# u_build_45w_power_supply.net
KiCad netlist of a schematic drawn in EAGLE
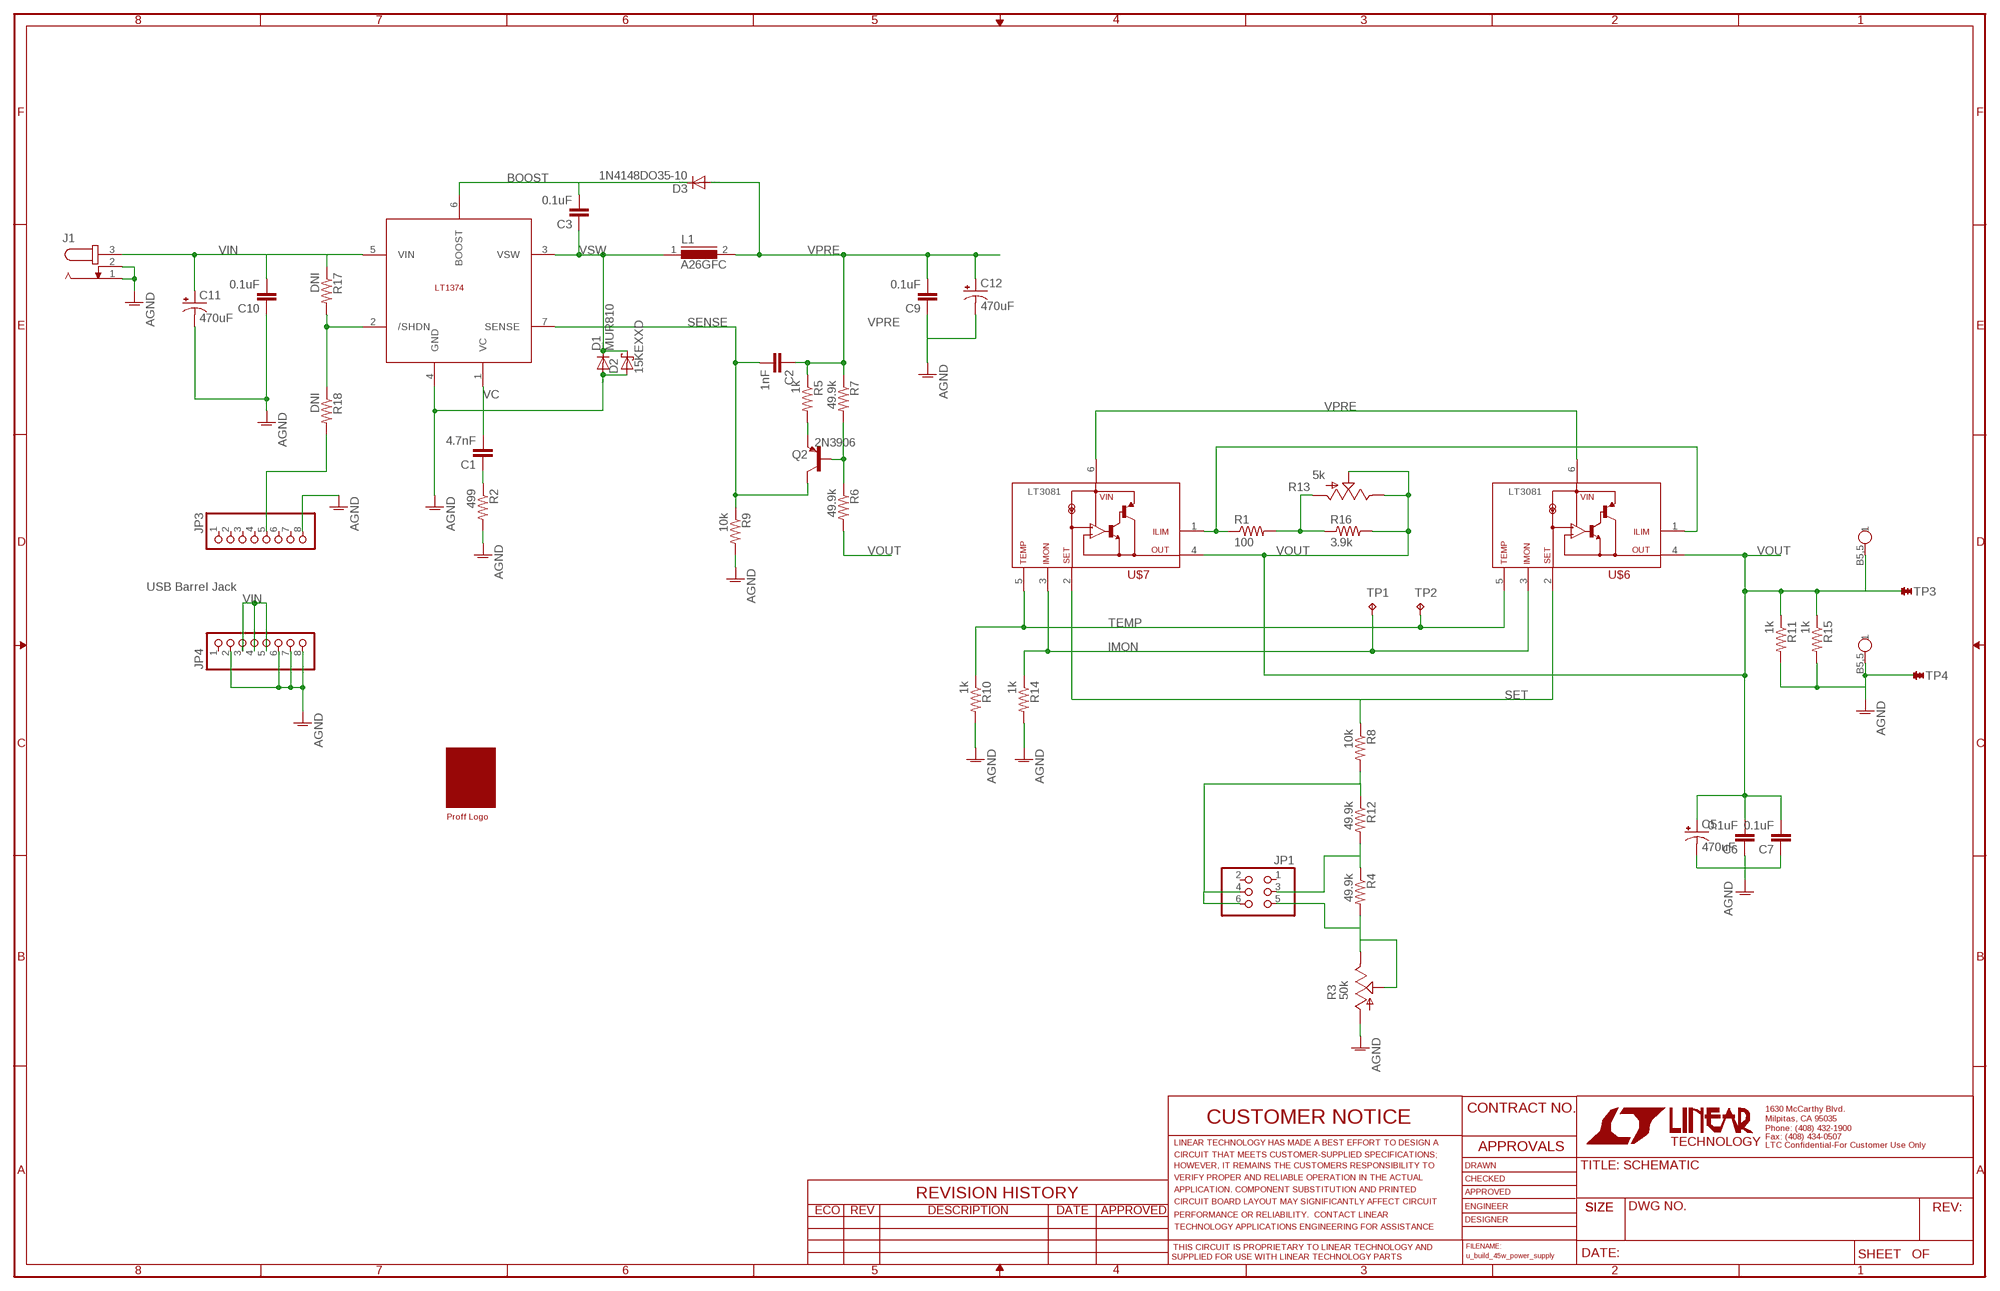
[diagram p0: schematic, sheet 1]

(export (version "E")
  (design (tool "Eeschema 10.0.6"))
  (components
    (comp (ref "C1")
      (value "4.7nF")
      (footprint "eagle-import:C050-025X075")
      (libsource (lib "eagle-import") (part "C-EU050-025X075"))
    )
    (comp (ref "C2")
      (value "1nF")
      (footprint "eagle-import:C050-025X075")
      (libsource (lib "eagle-import") (part "C-EU050-025X075"))
    )
    (comp (ref "C3")
      (value "0.1uF")
      (footprint "eagle-import:C050-025X075")
      (libsource (lib "eagle-import") (part "C-EU050-025X075"))
    )
    (comp (ref "C5")
      (value "470uF")
      (footprint "eagle-import:E5-10,5")
      (libsource (lib "eagle-import") (part "CPOL-USE5-10.5"))
    )
    (comp (ref "C6")
      (value "0.1uF")
      (footprint "eagle-import:C050-045X075")
      (libsource (lib "eagle-import") (part "C-EU050-045X075"))
    )
    (comp (ref "C7")
      (value "0.1uF")
      (footprint "eagle-import:C050-045X075")
      (libsource (lib "eagle-import") (part "C-EU050-045X075"))
    )
    (comp (ref "C9")
      (value "0.1uF")
      (footprint "eagle-import:C050-045X075")
      (libsource (lib "eagle-import") (part "C-EU050-045X075"))
    )
    (comp (ref "C10")
      (value "0.1uF")
      (footprint "eagle-import:C050-045X075")
      (libsource (lib "eagle-import") (part "C-EU050-045X075"))
    )
    (comp (ref "C11")
      (value "470uF")
      (footprint "eagle-import:E5-10,5")
      (libsource (lib "eagle-import") (part "CPOL-USE5-10.5"))
    )
    (comp (ref "C12")
      (value "470uF")
      (footprint "eagle-import:E5-10,5")
      (libsource (lib "eagle-import") (part "CPOL-USE5-10.5"))
    )
    (comp (ref "D1")
      (value "MUR810")
      (footprint "eagle-import:TO220ACS")
      (libsource (lib "eagle-import") (part "MUR810"))
    )
    (comp (ref "D2")
      (value "15KEXXD")
      (footprint "eagle-import:DO201T15")
      (libsource (lib "eagle-import") (part "15KEXXD"))
    )
    (comp (ref "D3")
      (value "1N4148DO35-10")
      (footprint "eagle-import:DO35-10")
      (libsource (lib "eagle-import") (part "1N4148DO35-10"))
    )
    (comp (ref "IC2")
      (value "LT1374TO220-7")
      (footprint "eagle-import:LT3081")
      (libsource (lib "eagle-import") (part "LT1374TO220-7"))
    )
    (comp (ref "J1")
      (value "JACK-PLUG0")
      (footprint "eagle-import:SPC4077")
      (libsource (lib "eagle-import") (part "JACK-PLUG0"))
    )
    (comp (ref "J5")
      (value "BAN_JACK1")
      (footprint "eagle-import:PC_BAN_JACK")
      (libsource (lib "eagle-import") (part "BAN_JACK1"))
    )
    (comp (ref "J6")
      (value "BAN_JACK1")
      (footprint "eagle-import:PC_BAN_JACK")
      (libsource (lib "eagle-import") (part "BAN_JACK1"))
    )
    (comp (ref "JP1")
      (value "PINHD-2X3")
      (footprint "eagle-import:2X03")
      (libsource (lib "eagle-import") (part "PINHD-2X3"))
    )
    (comp (ref "JP3")
      (value "PINHD-1X8")
      (footprint "eagle-import:1X08")
      (libsource (lib "eagle-import") (part "PINHD-1X8"))
    )
    (comp (ref "JP4")
      (value "PINHD-1X8")
      (footprint "eagle-import:1X08")
      (libsource (lib "eagle-import") (part "PINHD-1X8"))
    )
    (comp (ref "L1")
      (value "A26GFC")
      (footprint "eagle-import:A26GFC")
      (libsource (lib "eagle-import") (part "A26GFC"))
    )
    (comp (ref "Q2")
      (value "2N3906")
      (footprint "eagle-import:TO92")
      (libsource (lib "eagle-import") (part "2N3906"))
    )
    (comp (ref "R1")
      (value "100")
      (footprint "eagle-import:0207_10")
      (libsource (lib "eagle-import") (part "R-US_0207/10"))
    )
    (comp (ref "R2")
      (value "499")
      (footprint "eagle-import:0207_10")
      (libsource (lib "eagle-import") (part "R-US_0207/10"))
    )
    (comp (ref "R3")
      (value "50k")
      (footprint "eagle-import:RS3")
      (libsource (lib "eagle-import") (part "TRIM_US-RS3"))
    )
    (comp (ref "R4")
      (value "49.9k")
      (footprint "eagle-import:0207_10")
      (libsource (lib "eagle-import") (part "R-US_0207/10"))
    )
    (comp (ref "R5")
      (value "1k")
      (footprint "eagle-import:0207_10")
      (libsource (lib "eagle-import") (part "R-US_0207/10"))
    )
    (comp (ref "R6")
      (value "49.9k")
      (footprint "eagle-import:0207_10")
      (libsource (lib "eagle-import") (part "R-US_0207/10"))
    )
    (comp (ref "R7")
      (value "49.9k")
      (footprint "eagle-import:0207_10")
      (libsource (lib "eagle-import") (part "R-US_0207/10"))
    )
    (comp (ref "R8")
      (value "10k")
      (footprint "eagle-import:0207_10")
      (libsource (lib "eagle-import") (part "R-US_0207/10"))
    )
    (comp (ref "R9")
      (value "10k")
      (footprint "eagle-import:0207_10")
      (libsource (lib "eagle-import") (part "R-US_0207/10"))
    )
    (comp (ref "R10")
      (value "1k")
      (footprint "eagle-import:0207_10")
      (libsource (lib "eagle-import") (part "R-US_0207/10"))
    )
    (comp (ref "R11")
      (value "1k")
      (footprint "eagle-import:0207_10")
      (libsource (lib "eagle-import") (part "R-US_0207/10"))
    )
    (comp (ref "R12")
      (value "49.9k")
      (footprint "eagle-import:0207_10")
      (libsource (lib "eagle-import") (part "R-US_0207/10"))
    )
    (comp (ref "R13")
      (value "5k")
      (footprint "eagle-import:RS3")
      (libsource (lib "eagle-import") (part "TRIM_US-RS3"))
    )
    (comp (ref "R14")
      (value "1k")
      (footprint "eagle-import:0207_10")
      (libsource (lib "eagle-import") (part "R-US_0207/10"))
    )
    (comp (ref "R15")
      (value "1k")
      (footprint "eagle-import:0207_10")
      (libsource (lib "eagle-import") (part "R-US_0207/10"))
    )
    (comp (ref "R16")
      (value "3.9k")
      (footprint "eagle-import:0207_10")
      (libsource (lib "eagle-import") (part "R-US_0207/10"))
    )
    (comp (ref "R17")
      (value "DNI")
      (footprint "eagle-import:0207_10")
      (libsource (lib "eagle-import") (part "R-US_0207/10"))
    )
    (comp (ref "R18")
      (value "DNI")
      (footprint "eagle-import:0207_10")
      (libsource (lib "eagle-import") (part "R-US_0207/10"))
    )
    (comp (ref "TP1")
      (value "TPPAD1-13")
      (footprint "eagle-import:P1-13")
      (libsource (lib "eagle-import") (part "TPPAD1-13"))
    )
    (comp (ref "TP2")
      (value "TPPAD1-13")
      (footprint "eagle-import:P1-13")
      (libsource (lib "eagle-import") (part "TPPAD1-13"))
    )
    (comp (ref "TP3")
      (value "TURRET0.092")
      (footprint "eagle-import:TURRET_MILLMAX_2501-2")
      (libsource (lib "eagle-import") (part "TURRET0.092"))
    )
    (comp (ref "TP4")
      (value "TURRET0.092")
      (footprint "eagle-import:TURRET_MILLMAX_2501-2")
      (libsource (lib "eagle-import") (part "TURRET0.092"))
    )
    (comp (ref "U$1")
      (value "PROFF")
      (footprint "eagle-import:PROFF")
      (libsource (lib "eagle-import") (part "PROFF"))
    )
    (comp (ref "U$6")
      (value "LT3081")
      (footprint "eagle-import:LT3081")
      (libsource (lib "eagle-import") (part "LT3081"))
    )
    (comp (ref "U$7")
      (value "LT3081")
      (footprint "eagle-import:LT3081")
      (libsource (lib "eagle-import") (part "LT3081"))
    )
  )
  (nets
    (net (code "1") (name "/BOOST") (class "Default")
      (node (ref "C3") (pin "2") (pinfunction "2_2") (pintype "passive"))
      (node (ref "D3") (pin "C") (pinfunction "C_C") (pintype "passive"))
      (node (ref "IC2") (pin "6") (pinfunction "BOOST_6") (pintype "bidirectional"))
    )
    (net (code "2") (name "/IMON") (class "Default")
      (node (ref "R14") (pin "1") (pinfunction "1_1") (pintype "passive"))
      (node (ref "TP1") (pin "TP") (pinfunction "TP_TP") (pintype "input"))
      (node (ref "U$6") (pin "3") (pinfunction "IMON_3") (pintype "bidirectional"))
      (node (ref "U$7") (pin "3") (pinfunction "IMON_3") (pintype "bidirectional"))
    )
    (net (code "3") (name "/SENSE") (class "Default")
      (node (ref "C2") (pin "2") (pinfunction "2_2") (pintype "passive"))
      (node (ref "IC2") (pin "7") (pinfunction "SENSE_7") (pintype "bidirectional"))
      (node (ref "Q2") (pin "1") (pinfunction "C_1") (pintype "passive"))
      (node (ref "R9") (pin "1") (pinfunction "1_1") (pintype "passive"))
    )
    (net (code "4") (name "/SET") (class "Default")
      (node (ref "R8") (pin "1") (pinfunction "1_1") (pintype "passive"))
      (node (ref "U$6") (pin "2") (pinfunction "SET_2") (pintype "bidirectional"))
      (node (ref "U$7") (pin "2") (pinfunction "SET_2") (pintype "bidirectional"))
    )
    (net (code "5") (name "/TEMP") (class "Default")
      (node (ref "R10") (pin "1") (pinfunction "1_1") (pintype "passive"))
      (node (ref "TP2") (pin "TP") (pinfunction "TP_TP") (pintype "input"))
      (node (ref "U$6") (pin "5") (pinfunction "TEMP_5") (pintype "bidirectional"))
      (node (ref "U$7") (pin "5") (pinfunction "TEMP_5") (pintype "bidirectional"))
    )
    (net (code "6") (name "/VC") (class "Default")
      (node (ref "C1") (pin "2") (pinfunction "2_2") (pintype "passive"))
      (node (ref "IC2") (pin "1") (pinfunction "VC_1") (pintype "bidirectional"))
    )
    (net (code "7") (name "/VIN") (class "Default")
      (node (ref "C10") (pin "2") (pinfunction "2_2") (pintype "passive"))
      (node (ref "C11") (pin "+") (pinfunction "+_+") (pintype "passive"))
      (node (ref "IC2") (pin "5") (pinfunction "VIN_5") (pintype "bidirectional"))
      (node (ref "J1") (pin "3") (pinfunction "3_3") (pintype "passive"))
      (node (ref "JP4") (pin "3") (pinfunction "3_3") (pintype "passive"))
      (node (ref "JP4") (pin "4") (pinfunction "4_4") (pintype "passive"))
      (node (ref "JP4") (pin "5") (pinfunction "5_5") (pintype "passive"))
      (node (ref "R17") (pin "1") (pinfunction "1_1") (pintype "passive"))
    )
    (net (code "8") (name "/VOUT") (class "Default")
      (node (ref "C5") (pin "+") (pinfunction "+_+") (pintype "passive"))
      (node (ref "C6") (pin "2") (pinfunction "2_2") (pintype "passive"))
      (node (ref "C7") (pin "2") (pinfunction "2_2") (pintype "passive"))
      (node (ref "J5") (pin "B5,5") (pinfunction "1_B5,5") (pintype "passive"))
      (node (ref "R11") (pin "1") (pinfunction "1_1") (pintype "passive"))
      (node (ref "R13") (pin "E") (pinfunction "E_E") (pintype "passive"))
      (node (ref "R13") (pin "S") (pinfunction "S_S") (pintype "passive"))
      (node (ref "R15") (pin "1") (pinfunction "1_1") (pintype "passive"))
      (node (ref "R16") (pin "2") (pinfunction "2_2") (pintype "passive"))
      (node (ref "R6") (pin "2") (pinfunction "2_2") (pintype "passive"))
      (node (ref "TP3") (pin "1") (pinfunction "1_1") (pintype "passive"))
      (node (ref "U$6") (pin "4") (pinfunction "OUT_4") (pintype "bidirectional"))
      (node (ref "U$7") (pin "4") (pinfunction "OUT_4") (pintype "bidirectional"))
    )
    (net (code "9") (name "/VPRE") (class "Default")
      (node (ref "C12") (pin "+") (pinfunction "+_+") (pintype "passive"))
      (node (ref "C2") (pin "1") (pinfunction "1_1") (pintype "passive"))
      (node (ref "C9") (pin "2") (pinfunction "2_2") (pintype "passive"))
      (node (ref "D3") (pin "A") (pinfunction "A_A") (pintype "passive"))
      (node (ref "L1") (pin "2") (pinfunction "2_2") (pintype "passive"))
      (node (ref "R5") (pin "1") (pinfunction "1_1") (pintype "passive"))
      (node (ref "R7") (pin "1") (pinfunction "1_1") (pintype "passive"))
      (node (ref "U$6") (pin "6") (pinfunction "VIN_6") (pintype "bidirectional"))
      (node (ref "U$7") (pin "6") (pinfunction "VIN_6") (pintype "bidirectional"))
    )
    (net (code "10") (name "/VSW") (class "Default")
      (node (ref "C3") (pin "1") (pinfunction "1_1") (pintype "passive"))
      (node (ref "D1") (pin "C") (pinfunction "C_C") (pintype "passive"))
      (node (ref "D2") (pin "C") (pinfunction "C_C") (pintype "passive"))
      (node (ref "IC2") (pin "3") (pinfunction "VSW_3") (pintype "bidirectional"))
      (node (ref "L1") (pin "1") (pinfunction "1_1") (pintype "passive"))
    )
    (net (code "11") (name "AGND") (class "Default")
      (node (ref "C10") (pin "1") (pinfunction "1_1") (pintype "passive"))
      (node (ref "C11") (pin "-") (pinfunction "-_-") (pintype "passive"))
      (node (ref "C12") (pin "-") (pinfunction "-_-") (pintype "passive"))
      (node (ref "C5") (pin "-") (pinfunction "-_-") (pintype "passive"))
      (node (ref "C6") (pin "1") (pinfunction "1_1") (pintype "passive"))
      (node (ref "C7") (pin "1") (pinfunction "1_1") (pintype "passive"))
      (node (ref "C9") (pin "1") (pinfunction "1_1") (pintype "passive"))
      (node (ref "D1") (pin "A") (pinfunction "A_A") (pintype "passive"))
      (node (ref "D2") (pin "A") (pinfunction "A_A") (pintype "passive"))
      (node (ref "IC2") (pin "4") (pinfunction "GND_4") (pintype "bidirectional"))
      (node (ref "J1") (pin "1") (pinfunction "1_1") (pintype "passive"))
      (node (ref "J1") (pin "2") (pinfunction "2_2") (pintype "passive"))
      (node (ref "J6") (pin "B5,5") (pinfunction "1_B5,5") (pintype "passive"))
      (node (ref "JP3") (pin "8") (pinfunction "8_8") (pintype "passive"))
      (node (ref "JP4") (pin "2") (pinfunction "2_2") (pintype "passive"))
      (node (ref "JP4") (pin "6") (pinfunction "6_6") (pintype "passive"))
      (node (ref "JP4") (pin "7") (pinfunction "7_7") (pintype "passive"))
      (node (ref "JP4") (pin "8") (pinfunction "8_8") (pintype "passive"))
      (node (ref "R10") (pin "2") (pinfunction "2_2") (pintype "passive"))
      (node (ref "R11") (pin "2") (pinfunction "2_2") (pintype "passive"))
      (node (ref "R14") (pin "2") (pinfunction "2_2") (pintype "passive"))
      (node (ref "R15") (pin "2") (pinfunction "2_2") (pintype "passive"))
      (node (ref "R2") (pin "2") (pinfunction "2_2") (pintype "passive"))
      (node (ref "R3") (pin "A") (pinfunction "A_A") (pintype "passive"))
      (node (ref "R9") (pin "2") (pinfunction "2_2") (pintype "passive"))
      (node (ref "TP4") (pin "1") (pinfunction "1_1") (pintype "passive"))
    )
    (net (code "12") (name "Net-(C1-Pad1)") (class "Default")
      (node (ref "C1") (pin "1") (pinfunction "1_1") (pintype "passive"))
      (node (ref "R2") (pin "1") (pinfunction "1_1") (pintype "passive"))
    )
    (net (code "13") (name "Net-(IC2-{slash}SHDN)") (class "Default")
      (node (ref "IC2") (pin "2") (pinfunction "/SHDN_2") (pintype "bidirectional"))
      (node (ref "R17") (pin "2") (pinfunction "2_2") (pintype "passive"))
      (node (ref "R18") (pin "1") (pinfunction "1_1") (pintype "passive"))
    )
    (net (code "14") (name "Net-(JP1-Pad3)") (class "Default")
      (node (ref "JP1") (pin "3") (pinfunction "3_3") (pintype "passive"))
      (node (ref "R12") (pin "2") (pinfunction "2_2") (pintype "passive"))
      (node (ref "R4") (pin "1") (pinfunction "1_1") (pintype "passive"))
    )
    (net (code "15") (name "Net-(JP1-Pad4)") (class "Default")
      (node (ref "JP1") (pin "4") (pinfunction "4_4") (pintype "passive"))
      (node (ref "JP1") (pin "6") (pinfunction "6_6") (pintype "passive"))
      (node (ref "R12") (pin "1") (pinfunction "1_1") (pintype "passive"))
      (node (ref "R8") (pin "2") (pinfunction "2_2") (pintype "passive"))
    )
    (net (code "16") (name "Net-(JP1-Pad5)") (class "Default")
      (node (ref "JP1") (pin "5") (pinfunction "5_5") (pintype "passive"))
      (node (ref "R3") (pin "E") (pinfunction "E_E") (pintype "passive"))
      (node (ref "R3") (pin "S") (pinfunction "S_S") (pintype "passive"))
      (node (ref "R4") (pin "2") (pinfunction "2_2") (pintype "passive"))
    )
    (net (code "17") (name "Net-(JP3-Pad5)") (class "Default")
      (node (ref "JP3") (pin "5") (pinfunction "5_5") (pintype "passive"))
      (node (ref "R18") (pin "2") (pinfunction "2_2") (pintype "passive"))
    )
    (net (code "18") (name "Net-(Q2-B)") (class "Default")
      (node (ref "Q2") (pin "2") (pinfunction "B_2") (pintype "passive"))
      (node (ref "R6") (pin "1") (pinfunction "1_1") (pintype "passive"))
      (node (ref "R7") (pin "2") (pinfunction "2_2") (pintype "passive"))
    )
    (net (code "19") (name "Net-(Q2-E)") (class "Default")
      (node (ref "Q2") (pin "3") (pinfunction "E_3") (pintype "passive"))
      (node (ref "R5") (pin "2") (pinfunction "2_2") (pintype "passive"))
    )
    (net (code "20") (name "Net-(R1-Pad2)") (class "Default")
      (node (ref "R1") (pin "2") (pinfunction "2_2") (pintype "passive"))
      (node (ref "R13") (pin "A") (pinfunction "A_A") (pintype "passive"))
      (node (ref "R16") (pin "1") (pinfunction "1_1") (pintype "passive"))
    )
    (net (code "21") (name "Net-(U$6-ILIM)") (class "Default")
      (node (ref "R1") (pin "1") (pinfunction "1_1") (pintype "passive"))
      (node (ref "U$6") (pin "1") (pinfunction "ILIM_1") (pintype "bidirectional"))
      (node (ref "U$7") (pin "1") (pinfunction "ILIM_1") (pintype "bidirectional"))
    )
    (net (code "22") (name "unconnected-(JP1-Pad1)") (class "Default")
      (node (ref "JP1") (pin "1") (pinfunction "1_1") (pintype "passive"))
    )
    (net (code "23") (name "unconnected-(JP1-Pad2)") (class "Default")
      (node (ref "JP1") (pin "2") (pinfunction "2_2") (pintype "passive"))
    )
    (net (code "24") (name "unconnected-(JP3-Pad1)") (class "Default")
      (node (ref "JP3") (pin "1") (pinfunction "1_1") (pintype "passive"))
    )
    (net (code "25") (name "unconnected-(JP3-Pad2)") (class "Default")
      (node (ref "JP3") (pin "2") (pinfunction "2_2") (pintype "passive"))
    )
    (net (code "26") (name "unconnected-(JP3-Pad3)") (class "Default")
      (node (ref "JP3") (pin "3") (pinfunction "3_3") (pintype "passive"))
    )
    (net (code "27") (name "unconnected-(JP3-Pad4)") (class "Default")
      (node (ref "JP3") (pin "4") (pinfunction "4_4") (pintype "passive"))
    )
    (net (code "28") (name "unconnected-(JP3-Pad6)") (class "Default")
      (node (ref "JP3") (pin "6") (pinfunction "6_6") (pintype "passive"))
    )
    (net (code "29") (name "unconnected-(JP3-Pad7)") (class "Default")
      (node (ref "JP3") (pin "7") (pinfunction "7_7") (pintype "passive"))
    )
    (net (code "30") (name "unconnected-(JP4-Pad1)") (class "Default")
      (node (ref "JP4") (pin "1") (pinfunction "1_1") (pintype "passive"))
    )
  )
)
